# Adafruit_Bluefruit_LE_nRF8001.net
KiCad netlist of a schematic drawn in EAGLE
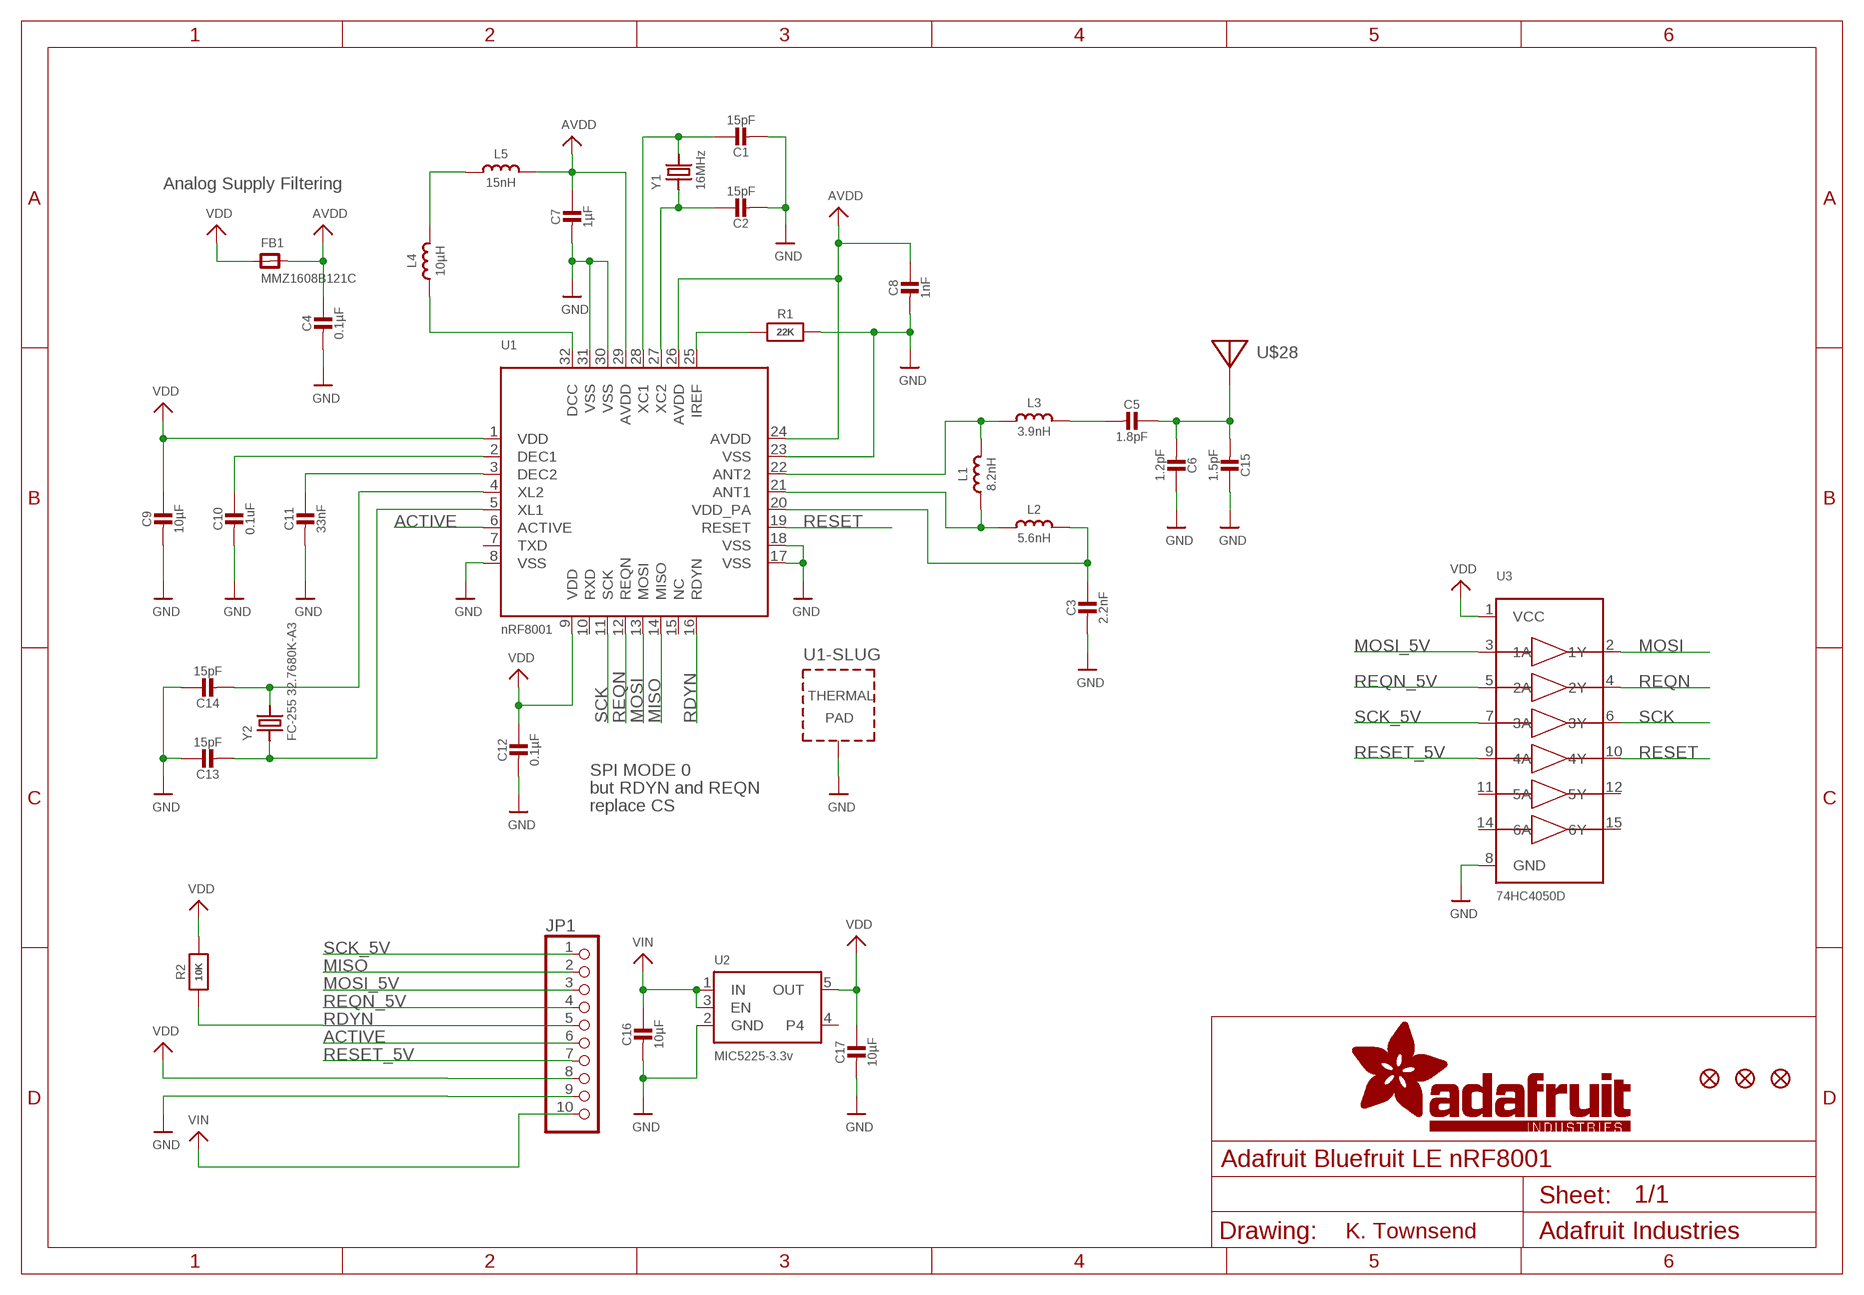
[diagram p0: schematic, sheet 1]

(export (version "E")
  (design (tool "Eeschema 10.0.6"))
  (components
    (comp (ref "C1")
      (value "15pF")
      (footprint "eagle-import:0805-NO")
      (libsource (lib "eagle-import") (part "CAP_CERAMIC0805-NOOUTLINE"))
    )
    (comp (ref "C2")
      (value "15pF")
      (footprint "eagle-import:0805-NO")
      (libsource (lib "eagle-import") (part "CAP_CERAMIC0805-NOOUTLINE"))
    )
    (comp (ref "C3")
      (value "2.2nF")
      (footprint "eagle-import:_0402")
      (libsource (lib "eagle-import") (part "CAP_CERAMIC_0402"))
    )
    (comp (ref "C4")
      (value "0.1µF")
      (footprint "eagle-import:0805-NO")
      (libsource (lib "eagle-import") (part "CAP_CERAMIC0805-NOOUTLINE"))
    )
    (comp (ref "C5")
      (value "1.8pF")
      (footprint "eagle-import:_0402MP")
      (libsource (lib "eagle-import") (part "CAP_CERAMIC_0402MP"))
    )
    (comp (ref "C6")
      (value "1.2pF")
      (footprint "eagle-import:_0402MP")
      (libsource (lib "eagle-import") (part "CAP_CERAMIC_0402MP"))
    )
    (comp (ref "C7")
      (value "1µF")
      (footprint "eagle-import:0805-NO")
      (libsource (lib "eagle-import") (part "CAP_CERAMIC0805-NOOUTLINE"))
    )
    (comp (ref "C8")
      (value "1nF")
      (footprint "eagle-import:_0603")
      (libsource (lib "eagle-import") (part "CAP_CERAMIC_0603"))
    )
    (comp (ref "C9")
      (value "10µF")
      (footprint "eagle-import:0805-NO")
      (libsource (lib "eagle-import") (part "CAP_CERAMIC0805-NOOUTLINE"))
    )
    (comp (ref "C10")
      (value "0.1uF")
      (footprint "eagle-import:0805-NO")
      (libsource (lib "eagle-import") (part "CAP_CERAMIC0805-NOOUTLINE"))
    )
    (comp (ref "C11")
      (value "33nF")
      (footprint "eagle-import:0805-NO")
      (libsource (lib "eagle-import") (part "CAP_CERAMIC0805-NOOUTLINE"))
    )
    (comp (ref "C12")
      (value "0.1µF")
      (footprint "eagle-import:0805-NO")
      (libsource (lib "eagle-import") (part "CAP_CERAMIC0805-NOOUTLINE"))
    )
    (comp (ref "C13")
      (value "15pF")
      (footprint "eagle-import:0805-NO")
      (libsource (lib "eagle-import") (part "CAP_CERAMIC0805-NOOUTLINE"))
    )
    (comp (ref "C14")
      (value "15pF")
      (footprint "eagle-import:0805-NO")
      (libsource (lib "eagle-import") (part "CAP_CERAMIC0805-NOOUTLINE"))
    )
    (comp (ref "C15")
      (value "1.5pF")
      (footprint "eagle-import:_0402MP")
      (libsource (lib "eagle-import") (part "CAP_CERAMIC_0402MP"))
    )
    (comp (ref "C16")
      (value "10µF")
      (footprint "eagle-import:0805-NO")
      (libsource (lib "eagle-import") (part "CAP_CERAMIC0805-NOOUTLINE"))
    )
    (comp (ref "C17")
      (value "10µF")
      (footprint "eagle-import:0805-NO")
      (libsource (lib "eagle-import") (part "CAP_CERAMIC0805-NOOUTLINE"))
    )
    (comp (ref "FB1")
      (value "MMZ1608B121C")
      (footprint "eagle-import:0805")
      (libsource (lib "eagle-import") (part "FERRITE0805"))
    )
    (comp (ref "FID1")
      (value "FIDUCIAL\"\"")
      (footprint "eagle-import:FIDUCIAL_1MM")
      (libsource (lib "eagle-import") (part "FIDUCIAL{dblquote}{dblquote}"))
    )
    (comp (ref "FID2")
      (value "FIDUCIAL\"\"")
      (footprint "eagle-import:FIDUCIAL_1MM")
      (libsource (lib "eagle-import") (part "FIDUCIAL{dblquote}{dblquote}"))
    )
    (comp (ref "FID3")
      (value "FIDUCIAL\"\"")
      (footprint "eagle-import:FIDUCIAL_1MM")
      (fields (field (name "BOM") "EXCLUDE"))
      (libsource (lib "eagle-import") (part "FIDUCIAL{dblquote}{dblquote}"))
    )
    (comp (ref "JP1")
      (value "HEADER-1X1070MIL")
      (footprint "eagle-import:1X10_ROUND70")
      (libsource (lib "eagle-import") (part "HEADER-1X1070MIL"))
    )
    (comp (ref "L1")
      (value "8.2nH")
      (footprint "eagle-import:_0402")
      (libsource (lib "eagle-import") (part "INDUCTOR_0402"))
    )
    (comp (ref "L2")
      (value "5.6nH")
      (footprint "eagle-import:_0402")
      (libsource (lib "eagle-import") (part "INDUCTOR_0402"))
    )
    (comp (ref "L3")
      (value "3.9nH")
      (footprint "eagle-import:_0402")
      (libsource (lib "eagle-import") (part "INDUCTOR_0402"))
    )
    (comp (ref "L4")
      (value "10µH")
      (footprint "eagle-import:_0603")
      (libsource (lib "eagle-import") (part "INDUCTOR_0603"))
    )
    (comp (ref "L5")
      (value "15nH")
      (footprint "eagle-import:_0603")
      (libsource (lib "eagle-import") (part "INDUCTOR_0603"))
    )
    (comp (ref "R1")
      (value "22K")
      (footprint "eagle-import:_0805MP")
      (libsource (lib "eagle-import") (part "RESISTOR_0805MP"))
    )
    (comp (ref "R2")
      (value "10K")
      (footprint "eagle-import:0805-NO")
      (libsource (lib "eagle-import") (part "RESISTOR0805_NOOUTLINE"))
    )
    (comp (ref "U$28")
      (value "ANTENNA_PCBNRF8001_1.6MM")
      (footprint "eagle-import:ANT_PCB_2.4GHZ_NRF8001_1.6MM_1OZ")
      (libsource (lib "eagle-import") (part "ANTENNA_PCBNRF8001_1.6MM"))
    )
    (comp (ref "U1")
      (value "nRF8001")
      (footprint "eagle-import:QFN32_5MM")
      (libsource (lib "eagle-import") (part "NRF8001"))
    )
    (comp (ref "U2")
      (value "MIC5225-3.3v")
      (footprint "eagle-import:SOT23-5")
      (libsource (lib "eagle-import") (part "VREG_SOT23-5"))
    )
    (comp (ref "U3")
      (value "74HC4050D")
      (footprint "eagle-import:TSSOP16")
      (libsource (lib "eagle-import") (part "74HC4050DTSSOP"))
    )
    (comp (ref "Y1")
      (value "16MHz")
      (footprint "eagle-import:CRYSTAL_2.5X2")
      (libsource (lib "eagle-import") (part "CRYSTAL2.5X2.0"))
    )
    (comp (ref "Y2")
      (value "FC-255 32.7680K-A3")
      (footprint "eagle-import:CRYSTAL_4.9X1.8")
      (libsource (lib "eagle-import") (part "CRYSTAL4.9X1.8"))
    )
  )
  (nets
    (net (code "1") (name "/ACTIVE") (class "Default")
      (node (ref "JP1") (pin "6") (pinfunction "6_6") (pintype "passive"))
      (node (ref "U1") (pin "6") (pinfunction "ACTIVE_6") (pintype "output"))
    )
    (net (code "2") (name "/MISO") (class "Default")
      (node (ref "JP1") (pin "2") (pinfunction "2_2") (pintype "passive"))
      (node (ref "U1") (pin "14") (pinfunction "MISO_14") (pintype "output"))
    )
    (net (code "3") (name "/MOSI") (class "Default")
      (node (ref "U1") (pin "13") (pinfunction "MOSI_13") (pintype "input"))
      (node (ref "U3") (pin "2") (pinfunction "1Y_2") (pintype "bidirectional"))
    )
    (net (code "4") (name "/MOSI_5V") (class "Default")
      (node (ref "JP1") (pin "3") (pinfunction "3_3") (pintype "passive"))
      (node (ref "U3") (pin "3") (pinfunction "1A_3") (pintype "bidirectional"))
    )
    (net (code "5") (name "/RDYN") (class "Default")
      (node (ref "JP1") (pin "5") (pinfunction "5_5") (pintype "passive"))
      (node (ref "R2") (pin "1") (pinfunction "1_1") (pintype "passive"))
      (node (ref "U1") (pin "16") (pinfunction "RDYN_16") (pintype "output"))
    )
    (net (code "6") (name "/REQN") (class "Default")
      (node (ref "U1") (pin "12") (pinfunction "REQN_12") (pintype "input"))
      (node (ref "U3") (pin "4") (pinfunction "2Y_4") (pintype "bidirectional"))
    )
    (net (code "7") (name "/REQN_5V") (class "Default")
      (node (ref "JP1") (pin "4") (pinfunction "4_4") (pintype "passive"))
      (node (ref "U3") (pin "5") (pinfunction "2A_5") (pintype "bidirectional"))
    )
    (net (code "8") (name "/RESET") (class "Default")
      (node (ref "U1") (pin "19") (pinfunction "RESET_19") (pintype "input"))
      (node (ref "U3") (pin "10") (pinfunction "4Y_10") (pintype "bidirectional"))
    )
    (net (code "9") (name "/RESET_5V") (class "Default")
      (node (ref "JP1") (pin "7") (pinfunction "7_7") (pintype "passive"))
      (node (ref "U3") (pin "9") (pinfunction "4A_9") (pintype "bidirectional"))
    )
    (net (code "10") (name "/SCK") (class "Default")
      (node (ref "U1") (pin "11") (pinfunction "SCK_11") (pintype "input"))
      (node (ref "U3") (pin "6") (pinfunction "3Y_6") (pintype "bidirectional"))
    )
    (net (code "11") (name "/SCK_5V") (class "Default")
      (node (ref "JP1") (pin "1") (pinfunction "1_1") (pintype "passive"))
      (node (ref "U3") (pin "7") (pinfunction "3A_7") (pintype "bidirectional"))
    )
    (net (code "12") (name "AVDD") (class "Default")
      (node (ref "C4") (pin "1") (pinfunction "1_1") (pintype "passive"))
      (node (ref "C7") (pin "1") (pinfunction "1_1") (pintype "passive"))
      (node (ref "C8") (pin "1") (pinfunction "1_1") (pintype "passive"))
      (node (ref "FB1") (pin "2") (pinfunction "P$2_2") (pintype "passive"))
      (node (ref "L5") (pin "2") (pinfunction "2_2") (pintype "passive"))
      (node (ref "U1") (pin "24") (pinfunction "AVDD_24") (pintype "power_in"))
      (node (ref "U1") (pin "26") (pinfunction "AVDD_26") (pintype "power_in"))
      (node (ref "U1") (pin "29") (pinfunction "AVDD_29") (pintype "power_in"))
    )
    (net (code "13") (name "GND") (class "Default")
      (node (ref "C1") (pin "2") (pinfunction "2_2") (pintype "passive"))
      (node (ref "C10") (pin "2") (pinfunction "2_2") (pintype "passive"))
      (node (ref "C11") (pin "2") (pinfunction "2_2") (pintype "passive"))
      (node (ref "C12") (pin "2") (pinfunction "2_2") (pintype "passive"))
      (node (ref "C13") (pin "1") (pinfunction "1_1") (pintype "passive"))
      (node (ref "C14") (pin "1") (pinfunction "1_1") (pintype "passive"))
      (node (ref "C15") (pin "1") (pinfunction "1_1") (pintype "passive"))
      (node (ref "C16") (pin "2") (pinfunction "2_2") (pintype "passive"))
      (node (ref "C17") (pin "2") (pinfunction "2_2") (pintype "passive"))
      (node (ref "C2") (pin "2") (pinfunction "2_2") (pintype "passive"))
      (node (ref "C3") (pin "2") (pinfunction "2_2") (pintype "passive"))
      (node (ref "C4") (pin "2") (pinfunction "2_2") (pintype "passive"))
      (node (ref "C6") (pin "1") (pinfunction "1_1") (pintype "passive"))
      (node (ref "C7") (pin "2") (pinfunction "2_2") (pintype "passive"))
      (node (ref "C8") (pin "2") (pinfunction "2_2") (pintype "passive"))
      (node (ref "C9") (pin "2") (pinfunction "2_2") (pintype "passive"))
      (node (ref "JP1") (pin "9") (pinfunction "9_9") (pintype "passive"))
      (node (ref "R1") (pin "2") (pinfunction "2_2") (pintype "passive"))
      (node (ref "U1") (pin "17") (pinfunction "VSS_17") (pintype "power_in"))
      (node (ref "U1") (pin "18") (pinfunction "VSS_18") (pintype "power_in"))
      (node (ref "U1") (pin "23") (pinfunction "VSS_23") (pintype "power_in"))
      (node (ref "U1") (pin "30") (pinfunction "VSS_30") (pintype "power_in"))
      (node (ref "U1") (pin "31") (pinfunction "VSS_31") (pintype "power_in"))
      (node (ref "U1") (pin "33") (pinfunction "TP_33") (pintype "power_in"))
      (node (ref "U1") (pin "8") (pinfunction "VSS_8") (pintype "power_in"))
      (node (ref "U2") (pin "2") (pinfunction "GND_2") (pintype "power_in"))
      (node (ref "U3") (pin "8") (pinfunction "GND_8") (pintype "bidirectional"))
    )
    (net (code "14") (name "Net-(C5-Pad2)") (class "Default")
      (node (ref "C5") (pin "2") (pinfunction "2_2") (pintype "passive"))
      (node (ref "L3") (pin "2") (pinfunction "2_2") (pintype "passive"))
    )
    (net (code "15") (name "Net-(L4-Pad2)") (class "Default")
      (node (ref "L4") (pin "2") (pinfunction "2_2") (pintype "passive"))
      (node (ref "L5") (pin "1") (pinfunction "1_1") (pintype "passive"))
    )
    (net (code "16") (name "Net-(U$28-P$1)") (class "Default")
      (node (ref "C15") (pin "2") (pinfunction "2_2") (pintype "passive"))
      (node (ref "C5") (pin "1") (pinfunction "1_1") (pintype "passive"))
      (node (ref "C6") (pin "2") (pinfunction "2_2") (pintype "passive"))
      (node (ref "U$28") (pin "FEED") (pinfunction "P$1_FEED") (pintype "passive"))
    )
    (net (code "17") (name "Net-(U1B-ANT1)") (class "Default")
      (node (ref "L1") (pin "1") (pinfunction "1_1") (pintype "passive"))
      (node (ref "L2") (pin "1") (pinfunction "1_1") (pintype "passive"))
      (node (ref "U1") (pin "21") (pinfunction "ANT1_21") (pintype "bidirectional"))
    )
    (net (code "18") (name "Net-(U1B-ANT2)") (class "Default")
      (node (ref "L1") (pin "2") (pinfunction "2_2") (pintype "passive"))
      (node (ref "L3") (pin "1") (pinfunction "1_1") (pintype "passive"))
      (node (ref "U1") (pin "22") (pinfunction "ANT2_22") (pintype "bidirectional"))
    )
    (net (code "19") (name "Net-(U1B-DCC)") (class "Default")
      (node (ref "L4") (pin "1") (pinfunction "1_1") (pintype "passive"))
      (node (ref "U1") (pin "32") (pinfunction "DCC_32") (pintype "bidirectional"))
    )
    (net (code "20") (name "Net-(U1B-DEC1)") (class "Default")
      (node (ref "C10") (pin "1") (pinfunction "1_1") (pintype "passive"))
      (node (ref "U1") (pin "2") (pinfunction "DEC1_2") (pintype "bidirectional"))
    )
    (net (code "21") (name "Net-(U1B-DEC2)") (class "Default")
      (node (ref "C11") (pin "1") (pinfunction "1_1") (pintype "passive"))
      (node (ref "U1") (pin "3") (pinfunction "DEC2_3") (pintype "bidirectional"))
    )
    (net (code "22") (name "Net-(U1B-IREF)") (class "Default")
      (node (ref "R1") (pin "1") (pinfunction "1_1") (pintype "passive"))
      (node (ref "U1") (pin "25") (pinfunction "IREF_25") (pintype "output"))
    )
    (net (code "23") (name "Net-(U1B-VDD_PA)") (class "Default")
      (node (ref "C3") (pin "1") (pinfunction "1_1") (pintype "passive"))
      (node (ref "L2") (pin "2") (pinfunction "2_2") (pintype "passive"))
      (node (ref "U1") (pin "20") (pinfunction "VDD_PA_20") (pintype "bidirectional"))
    )
    (net (code "24") (name "Net-(U1B-XC1)") (class "Default")
      (node (ref "C1") (pin "1") (pinfunction "1_1") (pintype "passive"))
      (node (ref "U1") (pin "28") (pinfunction "XC1_28") (pintype "input"))
      (node (ref "Y1") (pin "3") (pinfunction "2_3") (pintype "passive"))
    )
    (net (code "25") (name "Net-(U1B-XC2)") (class "Default")
      (node (ref "C2") (pin "1") (pinfunction "1_1") (pintype "passive"))
      (node (ref "U1") (pin "27") (pinfunction "XC2_27") (pintype "output"))
      (node (ref "Y1") (pin "1") (pinfunction "1_1") (pintype "passive"))
    )
    (net (code "26") (name "Net-(U1B-XL1)") (class "Default")
      (node (ref "C13") (pin "2") (pinfunction "2_2") (pintype "passive"))
      (node (ref "U1") (pin "5") (pinfunction "XL1_5") (pintype "input"))
      (node (ref "Y2") (pin "1") (pinfunction "1_1") (pintype "passive"))
    )
    (net (code "27") (name "Net-(U1B-XL2)") (class "Default")
      (node (ref "C14") (pin "2") (pinfunction "2_2") (pintype "passive"))
      (node (ref "U1") (pin "4") (pinfunction "XL2_4") (pintype "output"))
      (node (ref "Y2") (pin "2") (pinfunction "2_2") (pintype "passive"))
    )
    (net (code "28") (name "VDD") (class "Default")
      (node (ref "C12") (pin "1") (pinfunction "1_1") (pintype "passive"))
      (node (ref "C17") (pin "1") (pinfunction "1_1") (pintype "passive"))
      (node (ref "C9") (pin "1") (pinfunction "1_1") (pintype "passive"))
      (node (ref "FB1") (pin "1") (pinfunction "P$1_1") (pintype "passive"))
      (node (ref "JP1") (pin "8") (pinfunction "8_8") (pintype "passive"))
      (node (ref "R2") (pin "2") (pinfunction "2_2") (pintype "passive"))
      (node (ref "U1") (pin "1") (pinfunction "VDD_1") (pintype "power_in"))
      (node (ref "U1") (pin "9") (pinfunction "VDD_9") (pintype "power_in"))
      (node (ref "U2") (pin "5") (pinfunction "OUT_5") (pintype "power_in"))
      (node (ref "U3") (pin "1") (pinfunction "VCC_1") (pintype "bidirectional"))
    )
    (net (code "29") (name "VIN") (class "Default")
      (node (ref "C16") (pin "1") (pinfunction "1_1") (pintype "passive"))
      (node (ref "JP1") (pin "10") (pinfunction "10_10") (pintype "passive"))
      (node (ref "U2") (pin "1") (pinfunction "IN_1") (pintype "power_in"))
      (node (ref "U2") (pin "3") (pinfunction "EN_3") (pintype "input"))
    )
    (net (code "30") (name "unconnected-(U1B-NC-Pad15)") (class "Default")
      (node (ref "U1") (pin "15") (pinfunction "NC_15") (pintype "no_connect"))
    )
    (net (code "31") (name "unconnected-(U1B-RXD-Pad10)") (class "Default")
      (node (ref "U1") (pin "10") (pinfunction "RXD_10") (pintype "input"))
    )
    (net (code "32") (name "unconnected-(U1B-TXD-Pad7)") (class "Default")
      (node (ref "U1") (pin "7") (pinfunction "TXD_7") (pintype "output"))
    )
    (net (code "33") (name "unconnected-(U2-P4-Pad4)") (class "Default")
      (node (ref "U2") (pin "4") (pinfunction "P4_4") (pintype "bidirectional"))
    )
    (net (code "34") (name "unconnected-(U3-5A-Pad11)") (class "Default")
      (node (ref "U3") (pin "11") (pinfunction "5A_11") (pintype "bidirectional"))
    )
    (net (code "35") (name "unconnected-(U3-5Y-Pad12)") (class "Default")
      (node (ref "U3") (pin "12") (pinfunction "5Y_12") (pintype "bidirectional"))
    )
    (net (code "36") (name "unconnected-(U3-6A-Pad14)") (class "Default")
      (node (ref "U3") (pin "14") (pinfunction "6A_14") (pintype "bidirectional"))
    )
    (net (code "37") (name "unconnected-(U3-6Y-Pad15)") (class "Default")
      (node (ref "U3") (pin "15") (pinfunction "6Y_15") (pintype "bidirectional"))
    )
  )
)
